# DoublePN-OK.net
KiCad netlist of a schematic drawn in EAGLE
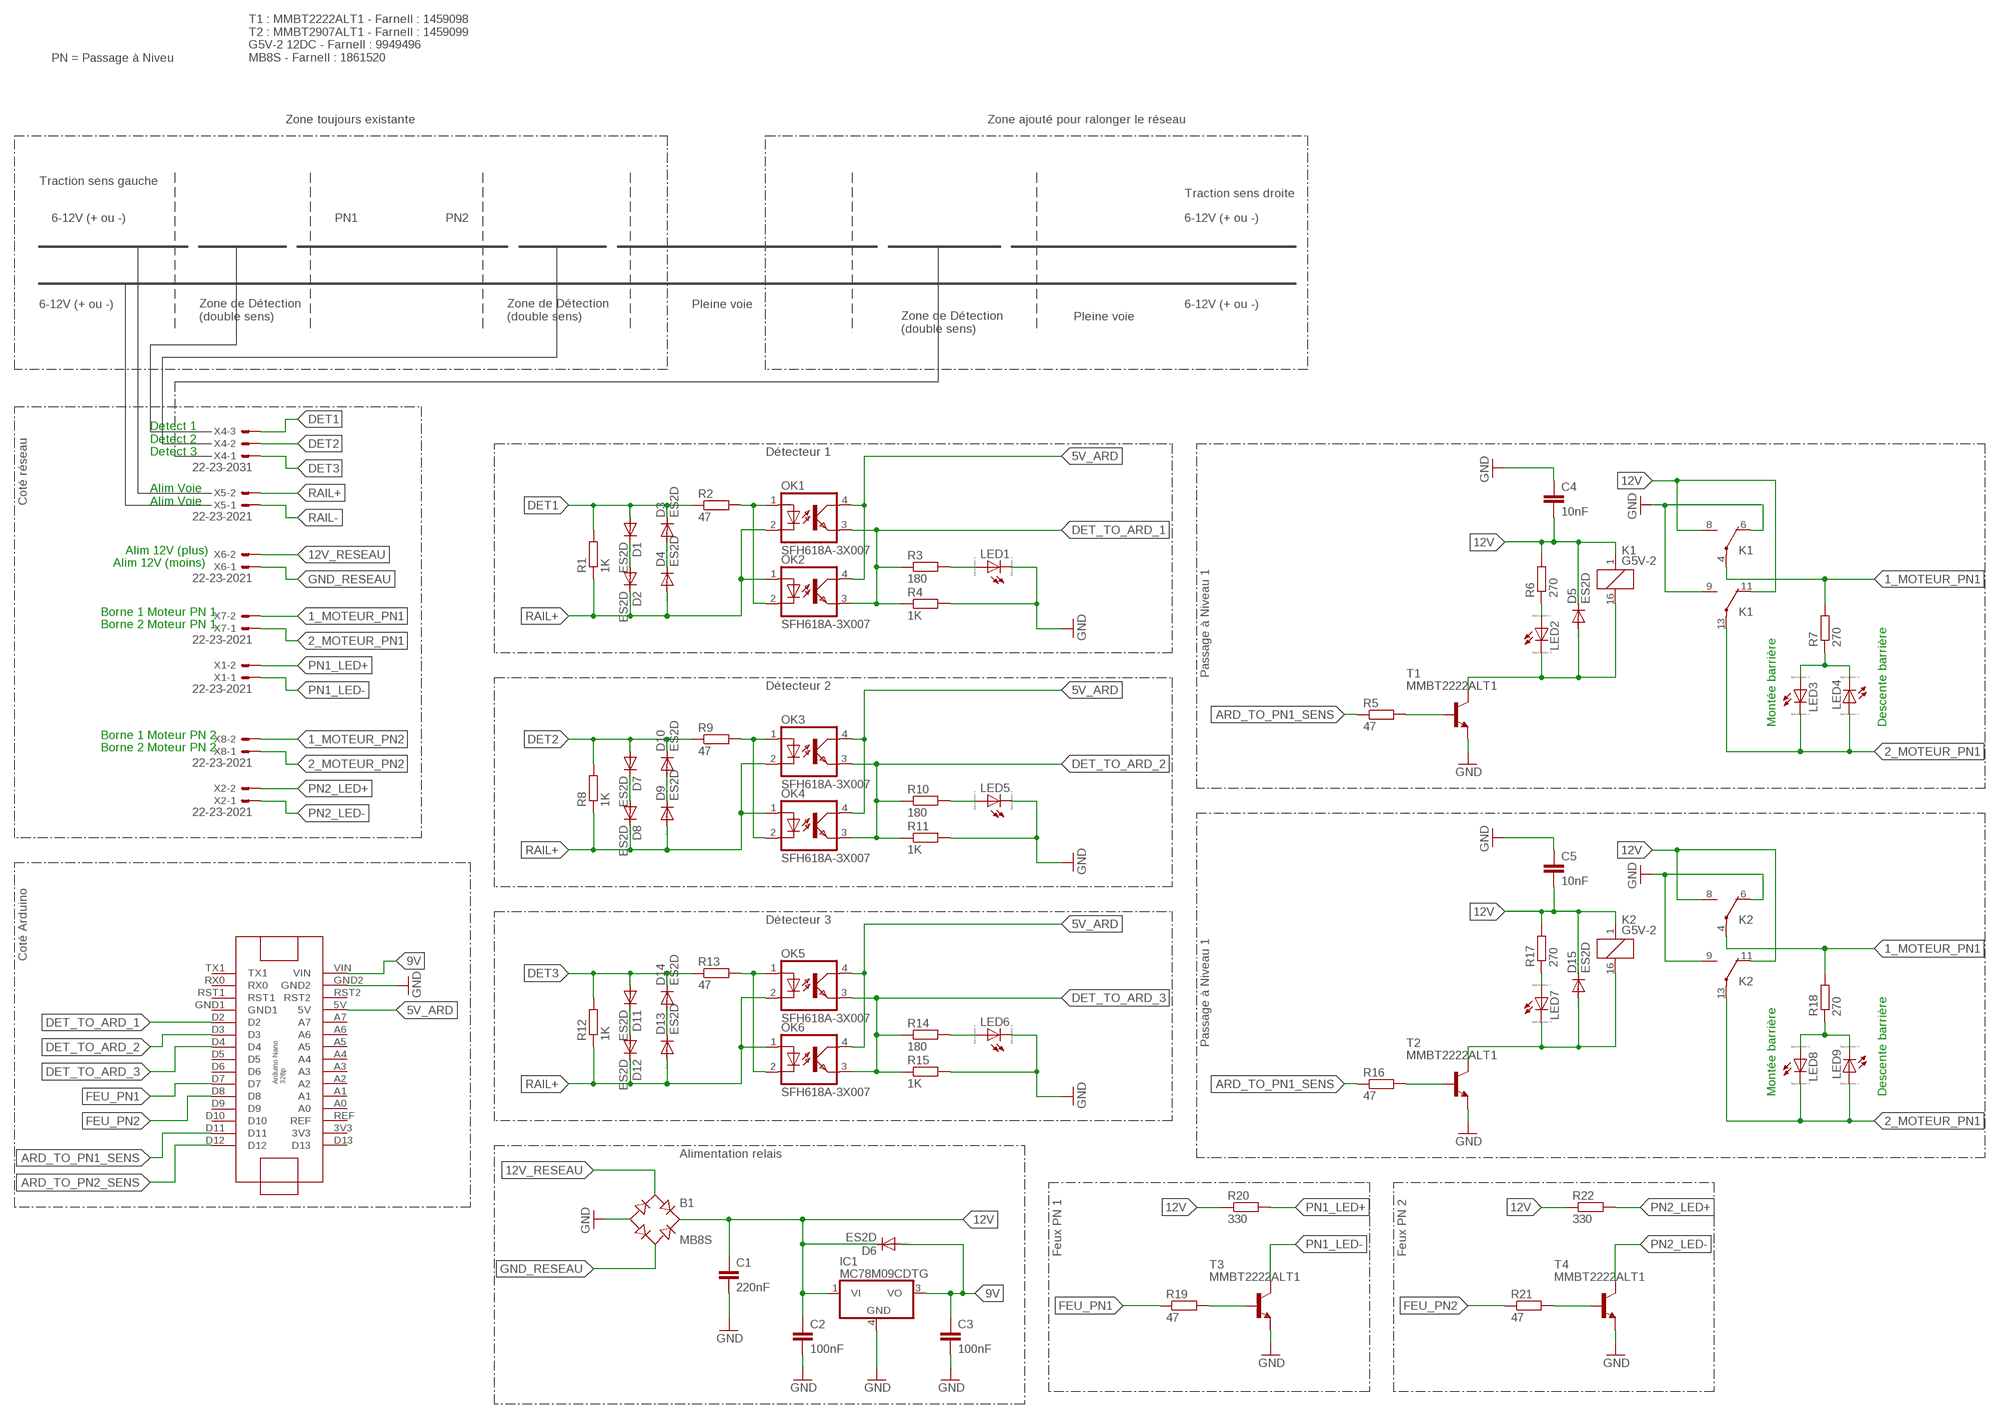
[diagram p0: schematic, sheet 1]

(export (version "E")
  (design (tool "Eeschema 10.0.6"))
  (components
    (comp (ref "ARDUINO-NANO1")
      (value "ARDUINO-NANO")
      (footprint "eagle-import:ARDUINO-NANO")
      (libsource (lib "eagle-import") (part "ARDUINO-NANO"))
    )
    (comp (ref "B1")
      (value "MB8S")
      (footprint "eagle-import:SOIC-4")
      (libsource (lib "eagle-import") (part "MBS8"))
    )
    (comp (ref "C1")
      (value "220nF")
      (footprint "eagle-import:C0805")
      (libsource (lib "eagle-import") (part "C-EUC0805"))
    )
    (comp (ref "C2")
      (value "100nF")
      (footprint "eagle-import:C0805")
      (libsource (lib "eagle-import") (part "C-EUC0805"))
    )
    (comp (ref "C3")
      (value "100nF")
      (footprint "eagle-import:C0805")
      (libsource (lib "eagle-import") (part "C-EUC0805"))
    )
    (comp (ref "C4")
      (value "10nF")
      (footprint "eagle-import:C0805")
      (libsource (lib "eagle-import") (part "C-EUC0805"))
    )
    (comp (ref "C5")
      (value "10nF")
      (footprint "eagle-import:C0805")
      (libsource (lib "eagle-import") (part "C-EUC0805"))
    )
    (comp (ref "D1")
      (value "ES2D")
      (footprint "eagle-import:SMB")
      (libsource (lib "eagle-import") (part "ES2D"))
    )
    (comp (ref "D2")
      (value "ES2D")
      (footprint "eagle-import:SMB")
      (libsource (lib "eagle-import") (part "ES2D"))
    )
    (comp (ref "D3")
      (value "ES2D")
      (footprint "eagle-import:SMB")
      (libsource (lib "eagle-import") (part "ES2D"))
    )
    (comp (ref "D4")
      (value "ES2D")
      (footprint "eagle-import:SMB")
      (libsource (lib "eagle-import") (part "ES2D"))
    )
    (comp (ref "D5")
      (value "ES2D")
      (footprint "eagle-import:SMB")
      (libsource (lib "eagle-import") (part "ES2D"))
    )
    (comp (ref "D6")
      (value "ES2D")
      (footprint "eagle-import:SMB")
      (libsource (lib "eagle-import") (part "ES2D"))
    )
    (comp (ref "D7")
      (value "ES2D")
      (footprint "eagle-import:SMB")
      (libsource (lib "eagle-import") (part "ES2D"))
    )
    (comp (ref "D8")
      (value "ES2D")
      (footprint "eagle-import:SMB")
      (libsource (lib "eagle-import") (part "ES2D"))
    )
    (comp (ref "D9")
      (value "ES2D")
      (footprint "eagle-import:SMB")
      (libsource (lib "eagle-import") (part "ES2D"))
    )
    (comp (ref "D10")
      (value "ES2D")
      (footprint "eagle-import:SMB")
      (libsource (lib "eagle-import") (part "ES2D"))
    )
    (comp (ref "D11")
      (value "ES2D")
      (footprint "eagle-import:SMB")
      (libsource (lib "eagle-import") (part "ES2D"))
    )
    (comp (ref "D12")
      (value "ES2D")
      (footprint "eagle-import:SMB")
      (libsource (lib "eagle-import") (part "ES2D"))
    )
    (comp (ref "D13")
      (value "ES2D")
      (footprint "eagle-import:SMB")
      (libsource (lib "eagle-import") (part "ES2D"))
    )
    (comp (ref "D14")
      (value "ES2D")
      (footprint "eagle-import:SMB")
      (libsource (lib "eagle-import") (part "ES2D"))
    )
    (comp (ref "D15")
      (value "ES2D")
      (footprint "eagle-import:SMB")
      (libsource (lib "eagle-import") (part "ES2D"))
    )
    (comp (ref "IC1")
      (value "MC78M09CDTG")
      (footprint "eagle-import:DPACK_3")
      (libsource (lib "eagle-import") (part "MC78M09CDTG"))
    )
    (comp (ref "K1")
      (value "G5V-2")
      (footprint "eagle-import:G5V-2")
      (fields (field (name "MPN") "G5V-2 5DC"))
      (libsource (lib "eagle-import") (part "G5V-2"))
    )
    (comp (ref "K2")
      (value "G5V-2")
      (footprint "eagle-import:G5V-2")
      (fields (field (name "MPN") "G5V-2 5DC"))
      (libsource (lib "eagle-import") (part "G5V-2"))
    )
    (comp (ref "LED1")
      (value "LED_ESML0603")
      (footprint "eagle-import:LED_SML0603")
      (libsource (lib "eagle-import") (part "LED_ESML0603"))
    )
    (comp (ref "LED2")
      (value "LED_ESML0603")
      (footprint "eagle-import:LED_SML0603")
      (libsource (lib "eagle-import") (part "LED_ESML0603"))
    )
    (comp (ref "LED3")
      (value "LED_ESML0603")
      (footprint "eagle-import:LED_SML0603")
      (libsource (lib "eagle-import") (part "LED_ESML0603"))
    )
    (comp (ref "LED4")
      (value "LED_ESML0603")
      (footprint "eagle-import:LED_SML0603")
      (libsource (lib "eagle-import") (part "LED_ESML0603"))
    )
    (comp (ref "LED5")
      (value "LED_ESML0603")
      (footprint "eagle-import:LED_SML0603")
      (libsource (lib "eagle-import") (part "LED_ESML0603"))
    )
    (comp (ref "LED6")
      (value "LED_ESML0603")
      (footprint "eagle-import:LED_SML0603")
      (libsource (lib "eagle-import") (part "LED_ESML0603"))
    )
    (comp (ref "LED7")
      (value "LED_ESML0603")
      (footprint "eagle-import:LED_SML0603")
      (libsource (lib "eagle-import") (part "LED_ESML0603"))
    )
    (comp (ref "LED8")
      (value "LED_ESML0603")
      (footprint "eagle-import:LED_SML0603")
      (libsource (lib "eagle-import") (part "LED_ESML0603"))
    )
    (comp (ref "LED9")
      (value "LED_ESML0603")
      (footprint "eagle-import:LED_SML0603")
      (libsource (lib "eagle-import") (part "LED_ESML0603"))
    )
    (comp (ref "OK1")
      (value "SFH618A-3X007")
      (footprint "eagle-import:SMD4-7")
      (libsource (lib "eagle-import") (part "SFH618?A-3X007"))
    )
    (comp (ref "OK2")
      (value "SFH618A-3X007")
      (footprint "eagle-import:SMD4-7")
      (libsource (lib "eagle-import") (part "SFH618?A-3X007"))
    )
    (comp (ref "OK3")
      (value "SFH618A-3X007")
      (footprint "eagle-import:SMD4-7")
      (libsource (lib "eagle-import") (part "SFH618?A-3X007"))
    )
    (comp (ref "OK4")
      (value "SFH618A-3X007")
      (footprint "eagle-import:SMD4-7")
      (libsource (lib "eagle-import") (part "SFH618?A-3X007"))
    )
    (comp (ref "OK5")
      (value "SFH618A-3X007")
      (footprint "eagle-import:SMD4-7")
      (libsource (lib "eagle-import") (part "SFH618?A-3X007"))
    )
    (comp (ref "OK6")
      (value "SFH618A-3X007")
      (footprint "eagle-import:SMD4-7")
      (libsource (lib "eagle-import") (part "SFH618?A-3X007"))
    )
    (comp (ref "R1")
      (value "1K")
      (footprint "eagle-import:R0805")
      (libsource (lib "eagle-import") (part "R-EU_R0805"))
    )
    (comp (ref "R2")
      (value "47")
      (footprint "eagle-import:R0805")
      (libsource (lib "eagle-import") (part "R-EU_R0805"))
    )
    (comp (ref "R3")
      (value "180")
      (footprint "eagle-import:R0805")
      (libsource (lib "eagle-import") (part "R-EU_R0805"))
    )
    (comp (ref "R4")
      (value "1K")
      (footprint "eagle-import:R0805")
      (libsource (lib "eagle-import") (part "R-EU_R0805"))
    )
    (comp (ref "R5")
      (value "47")
      (footprint "eagle-import:R0805")
      (libsource (lib "eagle-import") (part "R-EU_R0805"))
    )
    (comp (ref "R6")
      (value "270")
      (footprint "eagle-import:R0805")
      (libsource (lib "eagle-import") (part "R-EU_R0805"))
    )
    (comp (ref "R7")
      (value "270")
      (footprint "eagle-import:R0805")
      (libsource (lib "eagle-import") (part "R-EU_R0805"))
    )
    (comp (ref "R8")
      (value "1K")
      (footprint "eagle-import:R0805")
      (libsource (lib "eagle-import") (part "R-EU_R0805"))
    )
    (comp (ref "R9")
      (value "47")
      (footprint "eagle-import:R0805")
      (libsource (lib "eagle-import") (part "R-EU_R0805"))
    )
    (comp (ref "R10")
      (value "180")
      (footprint "eagle-import:R0805")
      (libsource (lib "eagle-import") (part "R-EU_R0805"))
    )
    (comp (ref "R11")
      (value "1K")
      (footprint "eagle-import:R0805")
      (libsource (lib "eagle-import") (part "R-EU_R0805"))
    )
    (comp (ref "R12")
      (value "1K")
      (footprint "eagle-import:R0805")
      (libsource (lib "eagle-import") (part "R-EU_R0805"))
    )
    (comp (ref "R13")
      (value "47")
      (footprint "eagle-import:R0805")
      (libsource (lib "eagle-import") (part "R-EU_R0805"))
    )
    (comp (ref "R14")
      (value "180")
      (footprint "eagle-import:R0805")
      (libsource (lib "eagle-import") (part "R-EU_R0805"))
    )
    (comp (ref "R15")
      (value "1K")
      (footprint "eagle-import:R0805")
      (libsource (lib "eagle-import") (part "R-EU_R0805"))
    )
    (comp (ref "R16")
      (value "47")
      (footprint "eagle-import:R0805")
      (libsource (lib "eagle-import") (part "R-EU_R0805"))
    )
    (comp (ref "R17")
      (value "270")
      (footprint "eagle-import:R0805")
      (libsource (lib "eagle-import") (part "R-EU_R0805"))
    )
    (comp (ref "R18")
      (value "270")
      (footprint "eagle-import:R0805")
      (libsource (lib "eagle-import") (part "R-EU_R0805"))
    )
    (comp (ref "R19")
      (value "47")
      (footprint "eagle-import:R0805")
      (libsource (lib "eagle-import") (part "R-EU_R0805"))
    )
    (comp (ref "R20")
      (value "330")
      (footprint "eagle-import:R0805")
      (libsource (lib "eagle-import") (part "R-EU_R0805"))
    )
    (comp (ref "R21")
      (value "47")
      (footprint "eagle-import:R0805")
      (libsource (lib "eagle-import") (part "R-EU_R0805"))
    )
    (comp (ref "R22")
      (value "330")
      (footprint "eagle-import:R0805")
      (libsource (lib "eagle-import") (part "R-EU_R0805"))
    )
    (comp (ref "T1")
      (value "MMBT2222ALT1")
      (footprint "eagle-import:SOT23-BEC")
      (libsource (lib "eagle-import") (part "-NPN-SOT23-BECMMBT2222ALT1"))
    )
    (comp (ref "T2")
      (value "MMBT2222ALT1")
      (footprint "eagle-import:SOT23-BEC")
      (libsource (lib "eagle-import") (part "-NPN-SOT23-BECMMBT2222ALT1"))
    )
    (comp (ref "T3")
      (value "MMBT2222ALT1")
      (footprint "eagle-import:SOT23-BEC")
      (libsource (lib "eagle-import") (part "-NPN-SOT23-BECMMBT2222ALT1"))
    )
    (comp (ref "T4")
      (value "MMBT2222ALT1")
      (footprint "eagle-import:SOT23-BEC")
      (libsource (lib "eagle-import") (part "-NPN-SOT23-BECMMBT2222ALT1"))
    )
    (comp (ref "X1")
      (value "22-23-2021")
      (footprint "eagle-import:22-23-2021")
      (fields (field (name "MF") "MOLEX"))
      (libsource (lib "eagle-import") (part "22-23-2021"))
    )
    (comp (ref "X2")
      (value "22-23-2021")
      (footprint "eagle-import:22-23-2021")
      (fields (field (name "MF") "MOLEX"))
      (libsource (lib "eagle-import") (part "22-23-2021"))
    )
    (comp (ref "X4")
      (value "22-23-2031")
      (footprint "eagle-import:22-23-2031")
      (fields (field (name "MF") "MOLEX"))
      (libsource (lib "eagle-import") (part "22-23-2031"))
    )
    (comp (ref "X5")
      (value "22-23-2021")
      (footprint "eagle-import:22-23-2021")
      (fields (field (name "MF") "MOLEX"))
      (libsource (lib "eagle-import") (part "22-23-2021"))
    )
    (comp (ref "X6")
      (value "22-23-2021")
      (footprint "eagle-import:22-23-2021")
      (fields (field (name "MF") "MOLEX"))
      (libsource (lib "eagle-import") (part "22-23-2021"))
    )
    (comp (ref "X7")
      (value "22-23-2021")
      (footprint "eagle-import:22-23-2021")
      (fields (field (name "MF") "MOLEX"))
      (libsource (lib "eagle-import") (part "22-23-2021"))
    )
    (comp (ref "X8")
      (value "22-23-2021")
      (footprint "eagle-import:22-23-2021")
      (fields (field (name "MF") "MOLEX"))
      (libsource (lib "eagle-import") (part "22-23-2021"))
    )
  )
  (nets
    (net (code "1") (name "1_MOTEUR_PN1") (class "Default")
      (node (ref "K1") (pin "4") (pinfunction "P_4") (pintype "passive"))
      (node (ref "K2") (pin "4") (pinfunction "P_4") (pintype "passive"))
      (node (ref "R18") (pin "2") (pinfunction "2_2") (pintype "passive"))
      (node (ref "R7") (pin "2") (pinfunction "2_2") (pintype "passive"))
      (node (ref "X7") (pin "2") (pinfunction "S_2") (pintype "passive"))
    )
    (net (code "2") (name "1_MOTEUR_PN2") (class "Default")
      (node (ref "X8") (pin "2") (pinfunction "S_2") (pintype "passive"))
    )
    (net (code "3") (name "2_MOTEUR_PN1") (class "Default")
      (node (ref "K1") (pin "13") (pinfunction "P_13") (pintype "passive"))
      (node (ref "K2") (pin "13") (pinfunction "P_13") (pintype "passive"))
      (node (ref "LED3") (pin "C") (pinfunction "C_C") (pintype "passive"))
      (node (ref "LED4") (pin "A") (pinfunction "A_A") (pintype "passive"))
      (node (ref "LED8") (pin "C") (pinfunction "C_C") (pintype "passive"))
      (node (ref "LED9") (pin "A") (pinfunction "A_A") (pintype "passive"))
      (node (ref "X7") (pin "1") (pinfunction "S_1") (pintype "passive"))
    )
    (net (code "4") (name "2_MOTEUR_PN2") (class "Default")
      (node (ref "X8") (pin "1") (pinfunction "S_1") (pintype "passive"))
    )
    (net (code "5") (name "5V_ARD") (class "Default")
      (node (ref "ARDUINO-NANO1") (pin "5V") (pinfunction "5V_5V") (pintype "bidirectional"))
      (node (ref "OK1") (pin "4") (pinfunction "COL_4") (pintype "passive"))
      (node (ref "OK2") (pin "4") (pinfunction "COL_4") (pintype "passive"))
      (node (ref "OK3") (pin "4") (pinfunction "COL_4") (pintype "passive"))
      (node (ref "OK4") (pin "4") (pinfunction "COL_4") (pintype "passive"))
      (node (ref "OK5") (pin "4") (pinfunction "COL_4") (pintype "passive"))
      (node (ref "OK6") (pin "4") (pinfunction "COL_4") (pintype "passive"))
    )
    (net (code "6") (name "9V") (class "Default")
      (node (ref "ARDUINO-NANO1") (pin "VIN") (pinfunction "VIN_VIN") (pintype "input"))
      (node (ref "C3") (pin "1") (pinfunction "1_1") (pintype "passive"))
      (node (ref "D6") (pin "A") (pinfunction "A_A") (pintype "passive"))
      (node (ref "IC1") (pin "3") (pinfunction "VO_3") (pintype "passive"))
    )
    (net (code "7") (name "12V") (class "Default")
      (node (ref "B1") (pin "+") (pinfunction "+_+") (pintype "passive"))
      (node (ref "C1") (pin "1") (pinfunction "1_1") (pintype "passive"))
      (node (ref "C2") (pin "1") (pinfunction "1_1") (pintype "passive"))
      (node (ref "C4") (pin "2") (pinfunction "2_2") (pintype "passive"))
      (node (ref "C5") (pin "2") (pinfunction "2_2") (pintype "passive"))
      (node (ref "D15") (pin "C") (pinfunction "C_C") (pintype "passive"))
      (node (ref "D5") (pin "C") (pinfunction "C_C") (pintype "passive"))
      (node (ref "D6") (pin "C") (pinfunction "C_C") (pintype "passive"))
      (node (ref "IC1") (pin "1") (pinfunction "VI_1") (pintype "input"))
      (node (ref "K1") (pin "1") (pinfunction "1_1") (pintype "passive"))
      (node (ref "K1") (pin "11") (pinfunction "O_11") (pintype "passive"))
      (node (ref "K1") (pin "8") (pinfunction "S_8") (pintype "passive"))
      (node (ref "K2") (pin "1") (pinfunction "1_1") (pintype "passive"))
      (node (ref "K2") (pin "11") (pinfunction "O_11") (pintype "passive"))
      (node (ref "K2") (pin "8") (pinfunction "S_8") (pintype "passive"))
      (node (ref "R17") (pin "2") (pinfunction "2_2") (pintype "passive"))
      (node (ref "R20") (pin "1") (pinfunction "1_1") (pintype "passive"))
      (node (ref "R22") (pin "1") (pinfunction "1_1") (pintype "passive"))
      (node (ref "R6") (pin "2") (pinfunction "2_2") (pintype "passive"))
    )
    (net (code "8") (name "12V_RESEAU") (class "Default")
      (node (ref "B1") (pin "~1") (pinfunction "AC1_~1") (pintype "passive"))
      (node (ref "X6") (pin "2") (pinfunction "S_2") (pintype "passive"))
    )
    (net (code "9") (name "ARD_TO_PN1_SENS") (class "Default")
      (node (ref "ARDUINO-NANO1") (pin "D11") (pinfunction "D11_D11") (pintype "bidirectional"))
      (node (ref "R16") (pin "1") (pinfunction "1_1") (pintype "passive"))
      (node (ref "R5") (pin "1") (pinfunction "1_1") (pintype "passive"))
    )
    (net (code "10") (name "ARD_TO_PN2_SENS") (class "Default")
      (node (ref "ARDUINO-NANO1") (pin "D12") (pinfunction "D12_D12") (pintype "bidirectional"))
    )
    (net (code "11") (name "DET1") (class "Default")
      (node (ref "D1") (pin "A") (pinfunction "A_A") (pintype "passive"))
      (node (ref "D3") (pin "C") (pinfunction "C_C") (pintype "passive"))
      (node (ref "R1") (pin "2") (pinfunction "2_2") (pintype "passive"))
      (node (ref "R2") (pin "1") (pinfunction "1_1") (pintype "passive"))
      (node (ref "X4") (pin "3") (pinfunction "S_3") (pintype "passive"))
    )
    (net (code "12") (name "DET2") (class "Default")
      (node (ref "D10") (pin "C") (pinfunction "C_C") (pintype "passive"))
      (node (ref "D7") (pin "A") (pinfunction "A_A") (pintype "passive"))
      (node (ref "R8") (pin "2") (pinfunction "2_2") (pintype "passive"))
      (node (ref "R9") (pin "1") (pinfunction "1_1") (pintype "passive"))
      (node (ref "X4") (pin "2") (pinfunction "S_2") (pintype "passive"))
    )
    (net (code "13") (name "DET3") (class "Default")
      (node (ref "D11") (pin "A") (pinfunction "A_A") (pintype "passive"))
      (node (ref "D14") (pin "C") (pinfunction "C_C") (pintype "passive"))
      (node (ref "R12") (pin "2") (pinfunction "2_2") (pintype "passive"))
      (node (ref "R13") (pin "1") (pinfunction "1_1") (pintype "passive"))
      (node (ref "X4") (pin "1") (pinfunction "S_1") (pintype "passive"))
    )
    (net (code "14") (name "DET_TO_ARD_1") (class "Default")
      (node (ref "ARDUINO-NANO1") (pin "D2") (pinfunction "D2_D2") (pintype "bidirectional"))
      (node (ref "OK1") (pin "3") (pinfunction "EMIT_3") (pintype "passive"))
      (node (ref "OK2") (pin "3") (pinfunction "EMIT_3") (pintype "passive"))
      (node (ref "R3") (pin "1") (pinfunction "1_1") (pintype "passive"))
      (node (ref "R4") (pin "1") (pinfunction "1_1") (pintype "passive"))
    )
    (net (code "15") (name "DET_TO_ARD_2") (class "Default")
      (node (ref "ARDUINO-NANO1") (pin "D3") (pinfunction "D3_D3") (pintype "bidirectional"))
      (node (ref "OK3") (pin "3") (pinfunction "EMIT_3") (pintype "passive"))
      (node (ref "OK4") (pin "3") (pinfunction "EMIT_3") (pintype "passive"))
      (node (ref "R10") (pin "1") (pinfunction "1_1") (pintype "passive"))
      (node (ref "R11") (pin "1") (pinfunction "1_1") (pintype "passive"))
    )
    (net (code "16") (name "DET_TO_ARD_3") (class "Default")
      (node (ref "ARDUINO-NANO1") (pin "D4") (pinfunction "D4_D4") (pintype "bidirectional"))
      (node (ref "OK5") (pin "3") (pinfunction "EMIT_3") (pintype "passive"))
      (node (ref "OK6") (pin "3") (pinfunction "EMIT_3") (pintype "passive"))
      (node (ref "R14") (pin "1") (pinfunction "1_1") (pintype "passive"))
      (node (ref "R15") (pin "1") (pinfunction "1_1") (pintype "passive"))
    )
    (net (code "17") (name "FEU_PN1") (class "Default")
      (node (ref "ARDUINO-NANO1") (pin "D7") (pinfunction "D7_D7") (pintype "bidirectional"))
      (node (ref "R19") (pin "1") (pinfunction "1_1") (pintype "passive"))
    )
    (net (code "18") (name "FEU_PN2") (class "Default")
      (node (ref "ARDUINO-NANO1") (pin "D8") (pinfunction "D8_D8") (pintype "bidirectional"))
      (node (ref "R21") (pin "1") (pinfunction "1_1") (pintype "passive"))
    )
    (net (code "19") (name "GND") (class "Default")
      (node (ref "ARDUINO-NANO1") (pin "GND2") (pinfunction "GND2_GND2") (pintype "bidirectional"))
      (node (ref "B1") (pin "-") (pinfunction "-_-") (pintype "passive"))
      (node (ref "C1") (pin "2") (pinfunction "2_2") (pintype "passive"))
      (node (ref "C2") (pin "2") (pinfunction "2_2") (pintype "passive"))
      (node (ref "C3") (pin "2") (pinfunction "2_2") (pintype "passive"))
      (node (ref "C4") (pin "1") (pinfunction "1_1") (pintype "passive"))
      (node (ref "C5") (pin "1") (pinfunction "1_1") (pintype "passive"))
      (node (ref "IC1") (pin "4") (pinfunction "GND_4") (pintype "passive"))
      (node (ref "K1") (pin "6") (pinfunction "O_6") (pintype "passive"))
      (node (ref "K1") (pin "9") (pinfunction "S_9") (pintype "passive"))
      (node (ref "K2") (pin "6") (pinfunction "O_6") (pintype "passive"))
      (node (ref "K2") (pin "9") (pinfunction "S_9") (pintype "passive"))
      (node (ref "LED1") (pin "C") (pinfunction "C_C") (pintype "passive"))
      (node (ref "LED5") (pin "C") (pinfunction "C_C") (pintype "passive"))
      (node (ref "LED6") (pin "C") (pinfunction "C_C") (pintype "passive"))
      (node (ref "R11") (pin "2") (pinfunction "2_2") (pintype "passive"))
      (node (ref "R15") (pin "2") (pinfunction "2_2") (pintype "passive"))
      (node (ref "R4") (pin "2") (pinfunction "2_2") (pintype "passive"))
      (node (ref "T1") (pin "E") (pinfunction "E_E") (pintype "passive"))
      (node (ref "T2") (pin "E") (pinfunction "E_E") (pintype "passive"))
      (node (ref "T3") (pin "E") (pinfunction "E_E") (pintype "passive"))
      (node (ref "T4") (pin "E") (pinfunction "E_E") (pintype "passive"))
    )
    (net (code "20") (name "GND_RESEAU") (class "Default")
      (node (ref "B1") (pin "~2") (pinfunction "AC2_~2") (pintype "passive"))
      (node (ref "X6") (pin "1") (pinfunction "S_1") (pintype "passive"))
    )
    (net (code "21") (name "Net-(D1-PadC)") (class "Default")
      (node (ref "D1") (pin "C") (pinfunction "C_C") (pintype "passive"))
      (node (ref "D2") (pin "A") (pinfunction "A_A") (pintype "passive"))
    )
    (net (code "22") (name "Net-(D3-PadA)") (class "Default")
      (node (ref "D3") (pin "A") (pinfunction "A_A") (pintype "passive"))
      (node (ref "D4") (pin "C") (pinfunction "C_C") (pintype "passive"))
    )
    (net (code "23") (name "Net-(D7-PadC)") (class "Default")
      (node (ref "D7") (pin "C") (pinfunction "C_C") (pintype "passive"))
      (node (ref "D8") (pin "A") (pinfunction "A_A") (pintype "passive"))
    )
    (net (code "24") (name "Net-(D10-PadA)") (class "Default")
      (node (ref "D10") (pin "A") (pinfunction "A_A") (pintype "passive"))
      (node (ref "D9") (pin "C") (pinfunction "C_C") (pintype "passive"))
    )
    (net (code "25") (name "Net-(D11-PadC)") (class "Default")
      (node (ref "D11") (pin "C") (pinfunction "C_C") (pintype "passive"))
      (node (ref "D12") (pin "A") (pinfunction "A_A") (pintype "passive"))
    )
    (net (code "26") (name "Net-(D13-PadC)") (class "Default")
      (node (ref "D13") (pin "C") (pinfunction "C_C") (pintype "passive"))
      (node (ref "D14") (pin "A") (pinfunction "A_A") (pintype "passive"))
    )
    (net (code "27") (name "Net-(K1C-2)") (class "Default")
      (node (ref "D5") (pin "A") (pinfunction "A_A") (pintype "passive"))
      (node (ref "K1") (pin "16") (pinfunction "2_16") (pintype "passive"))
      (node (ref "LED2") (pin "C") (pinfunction "C_C") (pintype "passive"))
      (node (ref "T1") (pin "C") (pinfunction "C_C") (pintype "passive"))
    )
    (net (code "28") (name "Net-(K2C-2)") (class "Default")
      (node (ref "D15") (pin "A") (pinfunction "A_A") (pintype "passive"))
      (node (ref "K2") (pin "16") (pinfunction "2_16") (pintype "passive"))
      (node (ref "LED7") (pin "C") (pinfunction "C_C") (pintype "passive"))
      (node (ref "T2") (pin "C") (pinfunction "C_C") (pintype "passive"))
    )
    (net (code "29") (name "Net-(LED1-PadA)") (class "Default")
      (node (ref "LED1") (pin "A") (pinfunction "A_A") (pintype "passive"))
      (node (ref "R3") (pin "2") (pinfunction "2_2") (pintype "passive"))
    )
    (net (code "30") (name "Net-(LED2-PadA)") (class "Default")
      (node (ref "LED2") (pin "A") (pinfunction "A_A") (pintype "passive"))
      (node (ref "R6") (pin "1") (pinfunction "1_1") (pintype "passive"))
    )
    (net (code "31") (name "Net-(LED3-PadA)") (class "Default")
      (node (ref "LED3") (pin "A") (pinfunction "A_A") (pintype "passive"))
      (node (ref "LED4") (pin "C") (pinfunction "C_C") (pintype "passive"))
      (node (ref "R7") (pin "1") (pinfunction "1_1") (pintype "passive"))
    )
    (net (code "32") (name "Net-(LED5-PadA)") (class "Default")
      (node (ref "LED5") (pin "A") (pinfunction "A_A") (pintype "passive"))
      (node (ref "R10") (pin "2") (pinfunction "2_2") (pintype "passive"))
    )
    (net (code "33") (name "Net-(LED6-PadA)") (class "Default")
      (node (ref "LED6") (pin "A") (pinfunction "A_A") (pintype "passive"))
      (node (ref "R14") (pin "2") (pinfunction "2_2") (pintype "passive"))
    )
    (net (code "34") (name "Net-(LED7-PadA)") (class "Default")
      (node (ref "LED7") (pin "A") (pinfunction "A_A") (pintype "passive"))
      (node (ref "R17") (pin "1") (pinfunction "1_1") (pintype "passive"))
    )
    (net (code "35") (name "Net-(LED8-PadA)") (class "Default")
      (node (ref "LED8") (pin "A") (pinfunction "A_A") (pintype "passive"))
      (node (ref "LED9") (pin "C") (pinfunction "C_C") (pintype "passive"))
      (node (ref "R18") (pin "1") (pinfunction "1_1") (pintype "passive"))
    )
    (net (code "36") (name "Net-(OK1-A)") (class "Default")
      (node (ref "OK1") (pin "1") (pinfunction "A_1") (pintype "passive"))
      (node (ref "OK2") (pin "2") (pinfunction "C_2") (pintype "passive"))
      (node (ref "R2") (pin "2") (pinfunction "2_2") (pintype "passive"))
    )
    (net (code "37") (name "Net-(OK3-A)") (class "Default")
      (node (ref "OK3") (pin "1") (pinfunction "A_1") (pintype "passive"))
      (node (ref "OK4") (pin "2") (pinfunction "C_2") (pintype "passive"))
      (node (ref "R9") (pin "2") (pinfunction "2_2") (pintype "passive"))
    )
    (net (code "38") (name "Net-(OK5-A)") (class "Default")
      (node (ref "OK5") (pin "1") (pinfunction "A_1") (pintype "passive"))
      (node (ref "OK6") (pin "2") (pinfunction "C_2") (pintype "passive"))
      (node (ref "R13") (pin "2") (pinfunction "2_2") (pintype "passive"))
    )
    (net (code "39") (name "Net-(R5-Pad2)") (class "Default")
      (node (ref "R5") (pin "2") (pinfunction "2_2") (pintype "passive"))
      (node (ref "T1") (pin "B") (pinfunction "B_B") (pintype "passive"))
    )
    (net (code "40") (name "Net-(R16-Pad2)") (class "Default")
      (node (ref "R16") (pin "2") (pinfunction "2_2") (pintype "passive"))
      (node (ref "T2") (pin "B") (pinfunction "B_B") (pintype "passive"))
    )
    (net (code "41") (name "Net-(R19-Pad2)") (class "Default")
      (node (ref "R19") (pin "2") (pinfunction "2_2") (pintype "passive"))
      (node (ref "T3") (pin "B") (pinfunction "B_B") (pintype "passive"))
    )
    (net (code "42") (name "Net-(R21-Pad2)") (class "Default")
      (node (ref "R21") (pin "2") (pinfunction "2_2") (pintype "passive"))
      (node (ref "T4") (pin "B") (pinfunction "B_B") (pintype "passive"))
    )
    (net (code "43") (name "PN1_LED+") (class "Default")
      (node (ref "R20") (pin "2") (pinfunction "2_2") (pintype "passive"))
      (node (ref "X1") (pin "2") (pinfunction "S_2") (pintype "passive"))
    )
    (net (code "44") (name "PN1_LED-") (class "Default")
      (node (ref "T3") (pin "C") (pinfunction "C_C") (pintype "passive"))
      (node (ref "X1") (pin "1") (pinfunction "S_1") (pintype "passive"))
    )
    (net (code "45") (name "PN2_LED+") (class "Default")
      (node (ref "R22") (pin "2") (pinfunction "2_2") (pintype "passive"))
      (node (ref "X2") (pin "2") (pinfunction "S_2") (pintype "passive"))
    )
    (net (code "46") (name "PN2_LED-") (class "Default")
      (node (ref "T4") (pin "C") (pinfunction "C_C") (pintype "passive"))
      (node (ref "X2") (pin "1") (pinfunction "S_1") (pintype "passive"))
    )
    (net (code "47") (name "RAIL+") (class "Default")
      (node (ref "D12") (pin "C") (pinfunction "C_C") (pintype "passive"))
      (node (ref "D13") (pin "A") (pinfunction "A_A") (pintype "passive"))
      (node (ref "D2") (pin "C") (pinfunction "C_C") (pintype "passive"))
      (node (ref "D4") (pin "A") (pinfunction "A_A") (pintype "passive"))
      (node (ref "D8") (pin "C") (pinfunction "C_C") (pintype "passive"))
      (node (ref "D9") (pin "A") (pinfunction "A_A") (pintype "passive"))
      (node (ref "OK1") (pin "2") (pinfunction "C_2") (pintype "passive"))
      (node (ref "OK2") (pin "1") (pinfunction "A_1") (pintype "passive"))
      (node (ref "OK3") (pin "2") (pinfunction "C_2") (pintype "passive"))
      (node (ref "OK4") (pin "1") (pinfunction "A_1") (pintype "passive"))
      (node (ref "OK5") (pin "2") (pinfunction "C_2") (pintype "passive"))
      (node (ref "OK6") (pin "1") (pinfunction "A_1") (pintype "passive"))
      (node (ref "R1") (pin "1") (pinfunction "1_1") (pintype "passive"))
      (node (ref "R12") (pin "1") (pinfunction "1_1") (pintype "passive"))
      (node (ref "R8") (pin "1") (pinfunction "1_1") (pintype "passive"))
      (node (ref "X5") (pin "2") (pinfunction "S_2") (pintype "passive"))
    )
    (net (code "48") (name "RAIL-") (class "Default")
      (node (ref "X5") (pin "1") (pinfunction "S_1") (pintype "passive"))
    )
    (net (code "49") (name "unconnected-(ARDUINO-NANO1-Pad3V3)") (class "Default")
      (node (ref "ARDUINO-NANO1") (pin "3V3") (pinfunction "3V3_3V3") (pintype "output"))
    )
    (net (code "50") (name "unconnected-(ARDUINO-NANO1-PadA0)") (class "Default")
      (node (ref "ARDUINO-NANO1") (pin "A0") (pinfunction "A0_A0") (pintype "bidirectional"))
    )
    (net (code "51") (name "unconnected-(ARDUINO-NANO1-PadA1)") (class "Default")
      (node (ref "ARDUINO-NANO1") (pin "A1") (pinfunction "A1_A1") (pintype "bidirectional"))
    )
    (net (code "52") (name "unconnected-(ARDUINO-NANO1-PadA2)") (class "Default")
      (node (ref "ARDUINO-NANO1") (pin "A2") (pinfunction "A2_A2") (pintype "bidirectional"))
    )
    (net (code "53") (name "unconnected-(ARDUINO-NANO1-PadA3)") (class "Default")
      (node (ref "ARDUINO-NANO1") (pin "A3") (pinfunction "A3_A3") (pintype "bidirectional"))
    )
    (net (code "54") (name "unconnected-(ARDUINO-NANO1-PadA4)") (class "Default")
      (node (ref "ARDUINO-NANO1") (pin "A4") (pinfunction "A4_A4") (pintype "bidirectional"))
    )
    (net (code "55") (name "unconnected-(ARDUINO-NANO1-PadA5)") (class "Default")
      (node (ref "ARDUINO-NANO1") (pin "A5") (pinfunction "A5_A5") (pintype "bidirectional"))
    )
    (net (code "56") (name "unconnected-(ARDUINO-NANO1-PadA6)") (class "Default")
      (node (ref "ARDUINO-NANO1") (pin "A6") (pinfunction "A6_A6") (pintype "bidirectional"))
    )
    (net (code "57") (name "unconnected-(ARDUINO-NANO1-PadA7)") (class "Default")
      (node (ref "ARDUINO-NANO1") (pin "A7") (pinfunction "A7_A7") (pintype "output"))
    )
    (net (code "58") (name "unconnected-(ARDUINO-NANO1-PadD5)") (class "Default")
      (node (ref "ARDUINO-NANO1") (pin "D5") (pinfunction "D5_D5") (pintype "bidirectional"))
    )
    (net (code "59") (name "unconnected-(ARDUINO-NANO1-PadD6)") (class "Default")
      (node (ref "ARDUINO-NANO1") (pin "D6") (pinfunction "D6_D6") (pintype "bidirectional"))
    )
    (net (code "60") (name "unconnected-(ARDUINO-NANO1-PadD9)") (class "Default")
      (node (ref "ARDUINO-NANO1") (pin "D9") (pinfunction "D9_D9") (pintype "bidirectional"))
    )
    (net (code "61") (name "unconnected-(ARDUINO-NANO1-PadD10)") (class "Default")
      (node (ref "ARDUINO-NANO1") (pin "D10") (pinfunction "D10_D10") (pintype "bidirectional"))
    )
    (net (code "62") (name "unconnected-(ARDUINO-NANO1-PadD13)") (class "Default")
      (node (ref "ARDUINO-NANO1") (pin "D13") (pinfunction "D13_D13") (pintype "bidirectional"))
    )
    (net (code "63") (name "unconnected-(ARDUINO-NANO1-PadGND1)") (class "Default")
      (node (ref "ARDUINO-NANO1") (pin "GND1") (pinfunction "GND1_GND1") (pintype "input"))
    )
    (net (code "64") (name "unconnected-(ARDUINO-NANO1-PadREF)") (class "Default")
      (node (ref "ARDUINO-NANO1") (pin "REF") (pinfunction "REF_REF") (pintype "output"))
    )
    (net (code "65") (name "unconnected-(ARDUINO-NANO1-PadRST1)") (class "Default")
      (node (ref "ARDUINO-NANO1") (pin "RST1") (pinfunction "RST1_RST1") (pintype "input"))
    )
    (net (code "66") (name "unconnected-(ARDUINO-NANO1-PadRST2)") (class "Default")
      (node (ref "ARDUINO-NANO1") (pin "RST2") (pinfunction "RST2_RST2") (pintype "bidirectional"))
    )
    (net (code "67") (name "unconnected-(ARDUINO-NANO1-PadRX0)") (class "Default")
      (node (ref "ARDUINO-NANO1") (pin "RX0") (pinfunction "RX0_RX0") (pintype "input"))
    )
    (net (code "68") (name "unconnected-(ARDUINO-NANO1-PadTX1)") (class "Default")
      (node (ref "ARDUINO-NANO1") (pin "TX1") (pinfunction "TX1_TX1") (pintype "output"))
    )
  )
)
